# Motor_Controller2.net
KiCad netlist of a schematic drawn in EAGLE
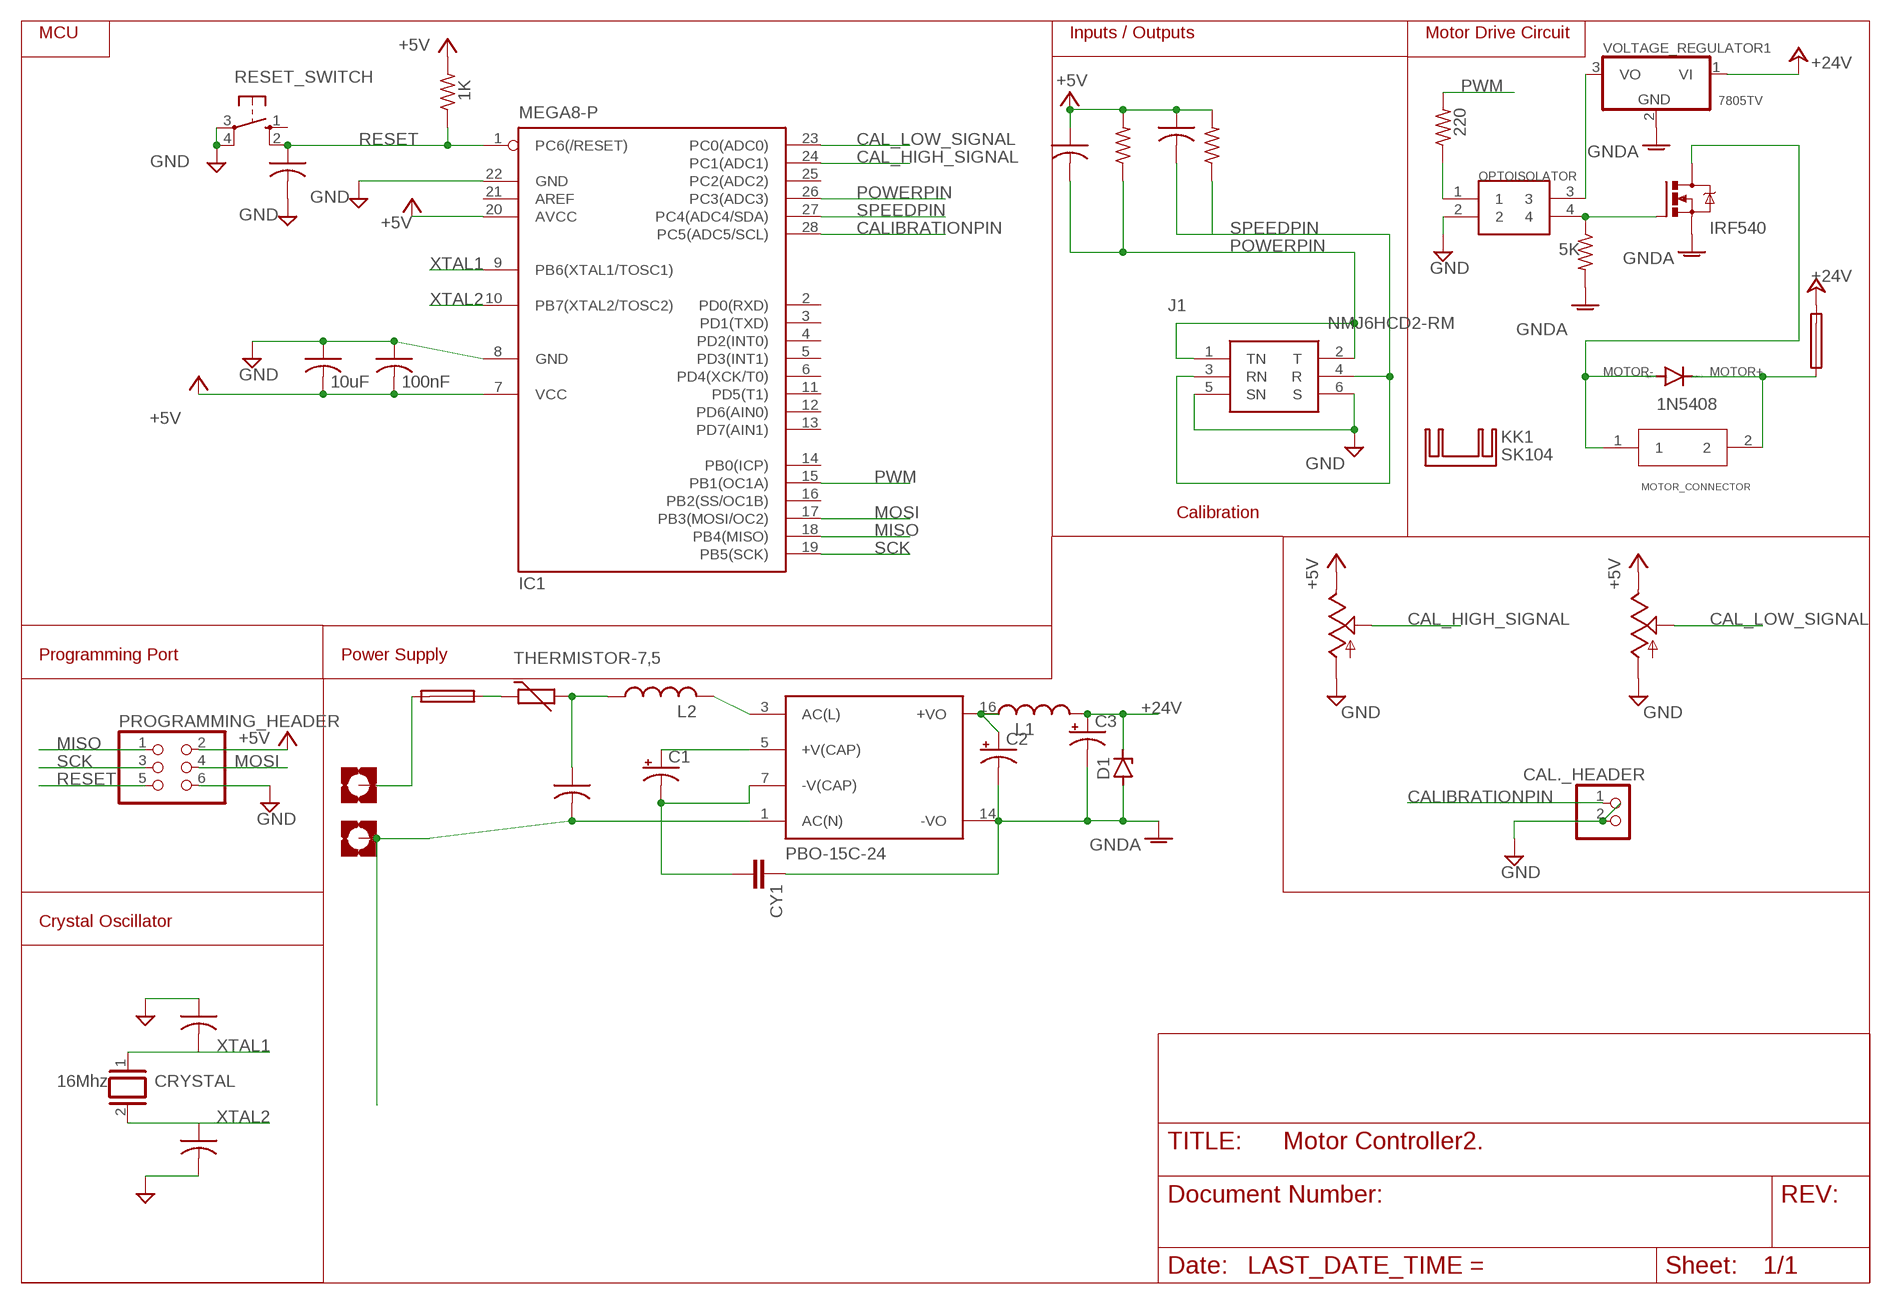
[diagram p0: schematic, sheet 1]

(export (version "E")
  (design (tool "Eeschema 10.0.6"))
  (components
    (comp (ref "1N5408")
      (value "1N5408")
      (footprint "eagle-import:DO201-15")
      (libsource (lib "eagle-import") (part "1N5400"))
    )
    (comp (ref "C1")
      (value "CPOL-USE5-13")
      (footprint "eagle-import:E5-13")
      (libsource (lib "eagle-import") (part "CPOL-USE5-13"))
    )
    (comp (ref "C2")
      (value "CPOL-USE5-10.5")
      (footprint "eagle-import:E5-10,5")
      (libsource (lib "eagle-import") (part "CPOL-USE5-10.5"))
    )
    (comp (ref "C3")
      (value "CPOL-USE5-10.5")
      (footprint "eagle-import:E5-10,5")
      (libsource (lib "eagle-import") (part "CPOL-USE5-10.5"))
    )
    (comp (ref "C4")
      (value "C-US150-091X182")
      (footprint "eagle-import:C150-091X182")
      (libsource (lib "eagle-import") (part "C-US150-091X182"))
    )
    (comp (ref "C6")
      (value "C-US025-024X044")
      (footprint "eagle-import:C025-024X044")
      (libsource (lib "eagle-import") (part "C-US025-024X044"))
    )
    (comp (ref "C10")
      (value "C-US025-024X044")
      (footprint "eagle-import:C025-024X044")
      (libsource (lib "eagle-import") (part "C-US025-024X044"))
    )
    (comp (ref "C11")
      (value "C-US025-024X044")
      (footprint "eagle-import:C025-024X044")
      (libsource (lib "eagle-import") (part "C-US025-024X044"))
    )
    (comp (ref "C12")
      (value "C-US025-024X044")
      (footprint "eagle-import:C025-024X044")
      (libsource (lib "eagle-import") (part "C-US025-024X044"))
    )
    (comp (ref "C13")
      (value "10uF")
      (footprint "eagle-import:C025-024X044")
      (libsource (lib "eagle-import") (part "C-US025-024X044"))
    )
    (comp (ref "C14")
      (value "100nF")
      (footprint "eagle-import:C025-024X044")
      (libsource (lib "eagle-import") (part "C-US025-024X044"))
    )
    (comp (ref "C15")
      (value "C-US025-024X044")
      (footprint "eagle-import:C025-024X044")
      (libsource (lib "eagle-import") (part "C-US025-024X044"))
    )
    (comp (ref "CAL._HEADER")
      (value "PINHD-1X2")
      (footprint "eagle-import:1X02")
      (libsource (lib "eagle-import") (part "PINHD-1X2"))
    )
    (comp (ref "CRYSTAL")
      (value "16Mhz")
      (footprint "eagle-import:QS")
      (libsource (lib "eagle-import") (part "XTAL/S"))
    )
    (comp (ref "CY1")
      (value "CYYC10B4")
      (footprint "eagle-import:YC10B4")
      (libsource (lib "eagle-import") (part "CYYC10B4"))
    )
    (comp (ref "D1")
      (value "ZENER-DIODEZD-7.5")
      (footprint "eagle-import:ZDIO-7.5")
      (libsource (lib "eagle-import") (part "ZENER-DIODEZD-7.5"))
    )
    (comp (ref "F1")
      (value "FUSESH22,5")
      (footprint "eagle-import:SH22,5")
      (libsource (lib "eagle-import") (part "FUSESH22,5"))
    )
    (comp (ref "F2")
      (value "FUSESH22,5")
      (footprint "eagle-import:SH22,5")
      (libsource (lib "eagle-import") (part "FUSESH22,5"))
    )
    (comp (ref "FAST")
      (value "TRIM_US-CT6")
      (footprint "eagle-import:CT6")
      (libsource (lib "eagle-import") (part "TRIM_US-CT6"))
    )
    (comp (ref "H1")
      (value "MOUNT-PAD-SQUARE3.6")
      (footprint "eagle-import:3,6-PAD-SQUARE")
      (libsource (lib "eagle-import") (part "MOUNT-PAD-SQUARE3.6"))
    )
    (comp (ref "H2")
      (value "MOUNT-PAD-SQUARE3.6")
      (footprint "eagle-import:3,6-PAD-SQUARE")
      (libsource (lib "eagle-import") (part "MOUNT-PAD-SQUARE3.6"))
    )
    (comp (ref "IC1")
      (value "MEGA8-P")
      (footprint "eagle-import:DIL28-3")
      (libsource (lib "eagle-import") (part "MEGA8-P"))
    )
    (comp (ref "J1")
      (value "NMJ6HCD2-RM")
      (footprint "eagle-import:NMJ6HCD2RM")
      (fields (field (name "MOUSER_PART_NUMBER") "568-NMJ6HCD2-RM"))
      (libsource (lib "eagle-import") (part "NMJ6HCD2-RM"))
    )
    (comp (ref "KK1")
      (value "SK104")
      (footprint "eagle-import:SK104")
      (libsource (lib "eagle-import") (part "SK104"))
    )
    (comp (ref "L1")
      (value "L-USTJ5-U1")
      (footprint "eagle-import:TJ5-U1")
      (libsource (lib "eagle-import") (part "L-USTJ5-U1"))
    )
    (comp (ref "L2")
      (value "L-US6000-XXX-RC")
      (footprint "eagle-import:6000-XXXX-RC")
      (libsource (lib "eagle-import") (part "L-US6000-XXX-RC"))
    )
    (comp (ref "MOTOR_CONNECTOR")
      (value "641963-1")
      (footprint "eagle-import:641963-1_TYC")
      (libsource (lib "eagle-import") (part "641963-1"))
    )
    (comp (ref "OPTOISOLATOR")
      (value "SFH619A")
      (footprint "eagle-import:SFH619A")
      (fields (field (name "OPTOISOLATOR") "SFH619A"))
      (libsource (lib "eagle-import") (part "SFH619A-ND"))
    )
    (comp (ref "PROGRAMMING_HEADER")
      (value "PINHD-2X3")
      (footprint "eagle-import:2X03")
      (libsource (lib "eagle-import") (part "PINHD-2X3"))
    )
    (comp (ref "PS1")
      (value "PBO-15C-24")
      (footprint "eagle-import:CONV_PBO-15C-24")
      (fields (field (name "MF") "CUI Inc."))
      (libsource (lib "eagle-import") (part "PBO-15C-24"))
    )
    (comp (ref "Q1")
      (value "IRF540")
      (footprint "eagle-import:TO220BV")
      (libsource (lib "eagle-import") (part "IRF540"))
    )
    (comp (ref "R1")
      (value "THERMISTOR-7,5")
      (footprint "eagle-import:R-7,5")
      (libsource (lib "eagle-import") (part "THERMISTOR-7,5"))
    )
    (comp (ref "R2")
      (value "1K")
      (footprint "eagle-import:0204_7")
      (libsource (lib "eagle-import") (part "R-US_0204/7"))
    )
    (comp (ref "R3")
      (value "R-US_0204/7")
      (footprint "eagle-import:0204_7")
      (libsource (lib "eagle-import") (part "R-US_0204/7"))
    )
    (comp (ref "R5")
      (value "220")
      (footprint "eagle-import:0204_7")
      (libsource (lib "eagle-import") (part "R-US_0204/7"))
    )
    (comp (ref "R6")
      (value "5K")
      (footprint "eagle-import:0204_7")
      (libsource (lib "eagle-import") (part "R-US_0204/7"))
    )
    (comp (ref "R7")
      (value "R-US_0204/7")
      (footprint "eagle-import:0204_7")
      (libsource (lib "eagle-import") (part "R-US_0204/7"))
    )
    (comp (ref "RESET_SWITCH")
      (value "10-XX")
      (footprint "eagle-import:B3F-10XX")
      (fields (field (name "MPN") "B3F-1000"))
      (libsource (lib "eagle-import") (part "10-XX"))
    )
    (comp (ref "SLOW")
      (value "TRIM_US-CT6")
      (footprint "eagle-import:CT6")
      (libsource (lib "eagle-import") (part "TRIM_US-CT6"))
    )
    (comp (ref "VOLTAGE_REGULATOR1")
      (value "7805TV")
      (footprint "eagle-import:TO220V")
      (libsource (lib "eagle-import") (part "78TV05"))
    )
  )
  (nets
    (net (code "1") (name "+5V") (class "Default")
      (node (ref "C10") (pin "1") (pinfunction "1_1") (pintype "passive"))
      (node (ref "C12") (pin "1") (pinfunction "1_1") (pintype "passive"))
      (node (ref "C13") (pin "2") (pinfunction "2_2") (pintype "passive"))
      (node (ref "C14") (pin "2") (pinfunction "2_2") (pintype "passive"))
      (node (ref "FAST") (pin "E") (pinfunction "E_E") (pintype "passive"))
      (node (ref "IC1") (pin "20") (pinfunction "AVCC_20") (pintype "power_in"))
      (node (ref "IC1") (pin "7") (pinfunction "VCC_7") (pintype "power_in"))
      (node (ref "PROGRAMMING_HEADER") (pin "2") (pinfunction "2_2") (pintype "passive"))
      (node (ref "R2") (pin "2") (pinfunction "2_2") (pintype "passive"))
      (node (ref "R3") (pin "2") (pinfunction "2_2") (pintype "passive"))
      (node (ref "R7") (pin "2") (pinfunction "2_2") (pintype "passive"))
      (node (ref "SLOW") (pin "E") (pinfunction "E_E") (pintype "passive"))
    )
    (net (code "2") (name "+24V") (class "Default")
      (node (ref "C3") (pin "+") (pinfunction "+_+") (pintype "passive"))
      (node (ref "D1") (pin "C") (pinfunction "C_C") (pintype "passive"))
      (node (ref "F1") (pin "2") (pinfunction "2_2") (pintype "passive"))
      (node (ref "L1") (pin "2") (pinfunction "2_2") (pintype "passive"))
      (node (ref "VOLTAGE_REGULATOR1") (pin "1") (pinfunction "VI_1") (pintype "input"))
    )
    (net (code "3") (name "/CALIBRATIONPIN") (class "Default")
      (node (ref "CAL._HEADER") (pin "1") (pinfunction "1_1") (pintype "passive"))
      (node (ref "IC1") (pin "28") (pinfunction "PC5(ADC5/SCL)_28") (pintype "bidirectional"))
    )
    (net (code "4") (name "/CAL_HIGH_SIGNAL") (class "Default")
      (node (ref "FAST") (pin "S") (pinfunction "S_S") (pintype "passive"))
      (node (ref "IC1") (pin "24") (pinfunction "PC1(ADC1)_24") (pintype "bidirectional"))
    )
    (net (code "5") (name "/CAL_LOW_SIGNAL") (class "Default")
      (node (ref "IC1") (pin "23") (pinfunction "PC0(ADC0)_23") (pintype "bidirectional"))
      (node (ref "SLOW") (pin "S") (pinfunction "S_S") (pintype "passive"))
    )
    (net (code "6") (name "/MISO") (class "Default")
      (node (ref "IC1") (pin "18") (pinfunction "PB4(MISO)_18") (pintype "bidirectional"))
      (node (ref "PROGRAMMING_HEADER") (pin "1") (pinfunction "1_1") (pintype "passive"))
    )
    (net (code "7") (name "/MOSI") (class "Default")
      (node (ref "IC1") (pin "17") (pinfunction "PB3(MOSI/OC2)_17") (pintype "bidirectional"))
      (node (ref "PROGRAMMING_HEADER") (pin "4") (pinfunction "4_4") (pintype "passive"))
    )
    (net (code "8") (name "/MOTOR+") (class "Default")
      (node (ref "1N5408") (pin "C") (pinfunction "C_C") (pintype "passive"))
      (node (ref "F1") (pin "1") (pinfunction "1_1") (pintype "passive"))
      (node (ref "MOTOR_CONNECTOR") (pin "2") (pinfunction "2_2") (pintype "passive"))
    )
    (net (code "9") (name "/MOTOR-") (class "Default")
      (node (ref "1N5408") (pin "A") (pinfunction "A_A") (pintype "passive"))
      (node (ref "MOTOR_CONNECTOR") (pin "1") (pinfunction "1_1") (pintype "passive"))
      (node (ref "Q1") (pin "D") (pinfunction "D_D") (pintype "passive"))
    )
    (net (code "10") (name "/POWERPIN") (class "Default")
      (node (ref "C10") (pin "2") (pinfunction "2_2") (pintype "passive"))
      (node (ref "IC1") (pin "26") (pinfunction "PC3(ADC3)_26") (pintype "bidirectional"))
      (node (ref "J1") (pin "1") (pinfunction "TN_1") (pintype "bidirectional"))
      (node (ref "J1") (pin "2") (pinfunction "T_2") (pintype "bidirectional"))
      (node (ref "R3") (pin "1") (pinfunction "1_1") (pintype "passive"))
    )
    (net (code "11") (name "/PWM") (class "Default")
      (node (ref "IC1") (pin "15") (pinfunction "PB1(OC1A)_15") (pintype "bidirectional"))
      (node (ref "R5") (pin "2") (pinfunction "2_2") (pintype "passive"))
    )
    (net (code "12") (name "/RESET") (class "Default")
      (node (ref "C11") (pin "1") (pinfunction "1_1") (pintype "passive"))
      (node (ref "IC1") (pin "1") (pinfunction "PC6(/RESET)_1") (pintype "bidirectional"))
      (node (ref "PROGRAMMING_HEADER") (pin "5") (pinfunction "5_5") (pintype "passive"))
      (node (ref "R2") (pin "1") (pinfunction "1_1") (pintype "passive"))
      (node (ref "RESET_SWITCH") (pin "2") (pinfunction "S1_2") (pintype "passive"))
    )
    (net (code "13") (name "/SCK") (class "Default")
      (node (ref "IC1") (pin "19") (pinfunction "PB5(SCK)_19") (pintype "bidirectional"))
      (node (ref "PROGRAMMING_HEADER") (pin "3") (pinfunction "3_3") (pintype "passive"))
    )
    (net (code "14") (name "/SPEEDPIN") (class "Default")
      (node (ref "C12") (pin "2") (pinfunction "2_2") (pintype "passive"))
      (node (ref "IC1") (pin "27") (pinfunction "PC4(ADC4/SDA)_27") (pintype "bidirectional"))
      (node (ref "J1") (pin "3") (pinfunction "RN_3") (pintype "bidirectional"))
      (node (ref "J1") (pin "4") (pinfunction "R_4") (pintype "bidirectional"))
      (node (ref "R7") (pin "1") (pinfunction "1_1") (pintype "passive"))
    )
    (net (code "15") (name "/XTAL1") (class "Default")
      (node (ref "C15") (pin "2") (pinfunction "2_2") (pintype "passive"))
      (node (ref "CRYSTAL") (pin "1") (pinfunction "1_1") (pintype "passive"))
      (node (ref "IC1") (pin "9") (pinfunction "PB6(XTAL1/TOSC1)_9") (pintype "bidirectional"))
    )
    (net (code "16") (name "/XTAL2") (class "Default")
      (node (ref "C6") (pin "1") (pinfunction "1_1") (pintype "passive"))
      (node (ref "CRYSTAL") (pin "2") (pinfunction "2_2") (pintype "passive"))
      (node (ref "IC1") (pin "10") (pinfunction "PB7(XTAL2/TOSC2)_10") (pintype "bidirectional"))
    )
    (net (code "17") (name "GND") (class "Default")
      (node (ref "C11") (pin "2") (pinfunction "2_2") (pintype "passive"))
      (node (ref "C13") (pin "1") (pinfunction "1_1") (pintype "passive"))
      (node (ref "C14") (pin "1") (pinfunction "1_1") (pintype "passive"))
      (node (ref "C15") (pin "1") (pinfunction "1_1") (pintype "passive"))
      (node (ref "C6") (pin "2") (pinfunction "2_2") (pintype "passive"))
      (node (ref "CAL._HEADER") (pin "2") (pinfunction "2_2") (pintype "passive"))
      (node (ref "FAST") (pin "A") (pinfunction "A_A") (pintype "passive"))
      (node (ref "IC1") (pin "22") (pinfunction "GND_22") (pintype "power_in"))
      (node (ref "IC1") (pin "8") (pinfunction "GND_8") (pintype "power_in"))
      (node (ref "J1") (pin "5") (pinfunction "SN_5") (pintype "bidirectional"))
      (node (ref "J1") (pin "6") (pinfunction "S_6") (pintype "bidirectional"))
      (node (ref "OPTOISOLATOR") (pin "2") (pinfunction "2_2") (pintype "bidirectional"))
      (node (ref "PROGRAMMING_HEADER") (pin "6") (pinfunction "6_6") (pintype "passive"))
      (node (ref "RESET_SWITCH") (pin "3") (pinfunction "P_3") (pintype "passive"))
      (node (ref "RESET_SWITCH") (pin "4") (pinfunction "P1_4") (pintype "passive"))
      (node (ref "SLOW") (pin "A") (pinfunction "A_A") (pintype "passive"))
    )
    (net (code "18") (name "GNDA") (class "Default")
      (node (ref "C2") (pin "-") (pinfunction "-_-") (pintype "passive"))
      (node (ref "C3") (pin "-") (pinfunction "-_-") (pintype "passive"))
      (node (ref "CY1") (pin "1") (pinfunction "1_1") (pintype "passive"))
      (node (ref "D1") (pin "A") (pinfunction "A_A") (pintype "passive"))
      (node (ref "PS1") (pin "14") (pinfunction "-VO_14") (pintype "output"))
      (node (ref "Q1") (pin "S") (pinfunction "S_S") (pintype "passive"))
      (node (ref "R6") (pin "2") (pinfunction "2_2") (pintype "passive"))
      (node (ref "VOLTAGE_REGULATOR1") (pin "2") (pinfunction "GND_2") (pintype "passive"))
    )
    (net (code "19") (name "Net-(C4-Pad1)") (class "Default")
      (node (ref "C4") (pin "1") (pinfunction "1_1") (pintype "passive"))
      (node (ref "L2") (pin "1") (pinfunction "1_1") (pintype "passive"))
      (node (ref "R1") (pin "2") (pinfunction "2_2") (pintype "passive"))
    )
    (net (code "20") (name "Net-(F2-Pad1)") (class "Default")
      (node (ref "F2") (pin "1") (pinfunction "1_1") (pintype "passive"))
      (node (ref "R1") (pin "1") (pinfunction "1_1") (pintype "passive"))
    )
    (net (code "21") (name "Net-(H1-MOUNT)") (class "Default")
      (node (ref "F2") (pin "2") (pinfunction "2_2") (pintype "passive"))
      (node (ref "H1") (pin "B3,6") (pinfunction "MOUNT_B3,6") (pintype "passive"))
    )
    (net (code "22") (name "Net-(H2-MOUNT)") (class "Default")
      (node (ref "C4") (pin "2") (pinfunction "2_2") (pintype "passive"))
      (node (ref "H2") (pin "B3,6") (pinfunction "MOUNT_B3,6") (pintype "passive"))
      (node (ref "PS1") (pin "1") (pinfunction "AC(N)_1") (pintype "input"))
    )
    (net (code "23") (name "Net-(OPTOISOLATOR-Pad1)") (class "Default")
      (node (ref "OPTOISOLATOR") (pin "1") (pinfunction "1_1") (pintype "bidirectional"))
      (node (ref "R5") (pin "1") (pinfunction "1_1") (pintype "passive"))
    )
    (net (code "24") (name "Net-(OPTOISOLATOR-Pad4)") (class "Default")
      (node (ref "OPTOISOLATOR") (pin "4") (pinfunction "4_4") (pintype "bidirectional"))
      (node (ref "Q1") (pin "G") (pinfunction "G_G") (pintype "passive"))
      (node (ref "R6") (pin "1") (pinfunction "1_1") (pintype "passive"))
    )
    (net (code "25") (name "Net-(PS1-+V(CAP))") (class "Default")
      (node (ref "C1") (pin "+") (pinfunction "+_+") (pintype "passive"))
      (node (ref "PS1") (pin "5") (pinfunction "+V(CAP)_5") (pintype "passive"))
    )
    (net (code "26") (name "Net-(PS1-+VO)") (class "Default")
      (node (ref "C2") (pin "+") (pinfunction "+_+") (pintype "passive"))
      (node (ref "L1") (pin "1") (pinfunction "1_1") (pintype "passive"))
      (node (ref "PS1") (pin "16") (pinfunction "+VO_16") (pintype "output"))
    )
    (net (code "27") (name "Net-(PS1--V(CAP))") (class "Default")
      (node (ref "C1") (pin "-") (pinfunction "-_-") (pintype "passive"))
      (node (ref "CY1") (pin "2") (pinfunction "2_2") (pintype "passive"))
      (node (ref "PS1") (pin "7") (pinfunction "-V(CAP)_7") (pintype "passive"))
    )
    (net (code "28") (name "Net-(PS1-AC(L))") (class "Default")
      (node (ref "L2") (pin "2") (pinfunction "2_2") (pintype "passive"))
      (node (ref "PS1") (pin "3") (pinfunction "AC(L)_3") (pintype "input"))
    )
    (net (code "29") (name "Net-(VOLTAGE_REGULATOR1-VO)") (class "Default")
      (node (ref "OPTOISOLATOR") (pin "3") (pinfunction "3_3") (pintype "bidirectional"))
      (node (ref "VOLTAGE_REGULATOR1") (pin "3") (pinfunction "VO_3") (pintype "passive"))
    )
    (net (code "30") (name "unconnected-(IC1-AREF-Pad21)") (class "Default")
      (node (ref "IC1") (pin "21") (pinfunction "AREF_21") (pintype "passive"))
    )
    (net (code "31") (name "unconnected-(IC1-PB0(ICP)-Pad14)") (class "Default")
      (node (ref "IC1") (pin "14") (pinfunction "PB0(ICP)_14") (pintype "bidirectional"))
    )
    (net (code "32") (name "unconnected-(IC1-PB2(SS{slash}OC1B)-Pad16)") (class "Default")
      (node (ref "IC1") (pin "16") (pinfunction "PB2(SS/OC1B)_16") (pintype "bidirectional"))
    )
    (net (code "33") (name "unconnected-(IC1-PC2(ADC2)-Pad25)") (class "Default")
      (node (ref "IC1") (pin "25") (pinfunction "PC2(ADC2)_25") (pintype "bidirectional"))
    )
    (net (code "34") (name "unconnected-(IC1-PD0(RXD)-Pad2)") (class "Default")
      (node (ref "IC1") (pin "2") (pinfunction "PD0(RXD)_2") (pintype "bidirectional"))
    )
    (net (code "35") (name "unconnected-(IC1-PD1(TXD)-Pad3)") (class "Default")
      (node (ref "IC1") (pin "3") (pinfunction "PD1(TXD)_3") (pintype "bidirectional"))
    )
    (net (code "36") (name "unconnected-(IC1-PD2(INT0)-Pad4)") (class "Default")
      (node (ref "IC1") (pin "4") (pinfunction "PD2(INT0)_4") (pintype "bidirectional"))
    )
    (net (code "37") (name "unconnected-(IC1-PD3(INT1)-Pad5)") (class "Default")
      (node (ref "IC1") (pin "5") (pinfunction "PD3(INT1)_5") (pintype "bidirectional"))
    )
    (net (code "38") (name "unconnected-(IC1-PD4(XCK{slash}T0)-Pad6)") (class "Default")
      (node (ref "IC1") (pin "6") (pinfunction "PD4(XCK/T0)_6") (pintype "bidirectional"))
    )
    (net (code "39") (name "unconnected-(IC1-PD5(T1)-Pad11)") (class "Default")
      (node (ref "IC1") (pin "11") (pinfunction "PD5(T1)_11") (pintype "bidirectional"))
    )
    (net (code "40") (name "unconnected-(IC1-PD6(AIN0)-Pad12)") (class "Default")
      (node (ref "IC1") (pin "12") (pinfunction "PD6(AIN0)_12") (pintype "bidirectional"))
    )
    (net (code "41") (name "unconnected-(IC1-PD7(AIN1)-Pad13)") (class "Default")
      (node (ref "IC1") (pin "13") (pinfunction "PD7(AIN1)_13") (pintype "bidirectional"))
    )
    (net (code "42") (name "unconnected-(RESET_SWITCH-S-Pad1)") (class "Default")
      (node (ref "RESET_SWITCH") (pin "1") (pinfunction "S_1") (pintype "passive"))
    )
  )
)
